# untitled2.net
KiCad netlist of a schematic drawn in EAGLE
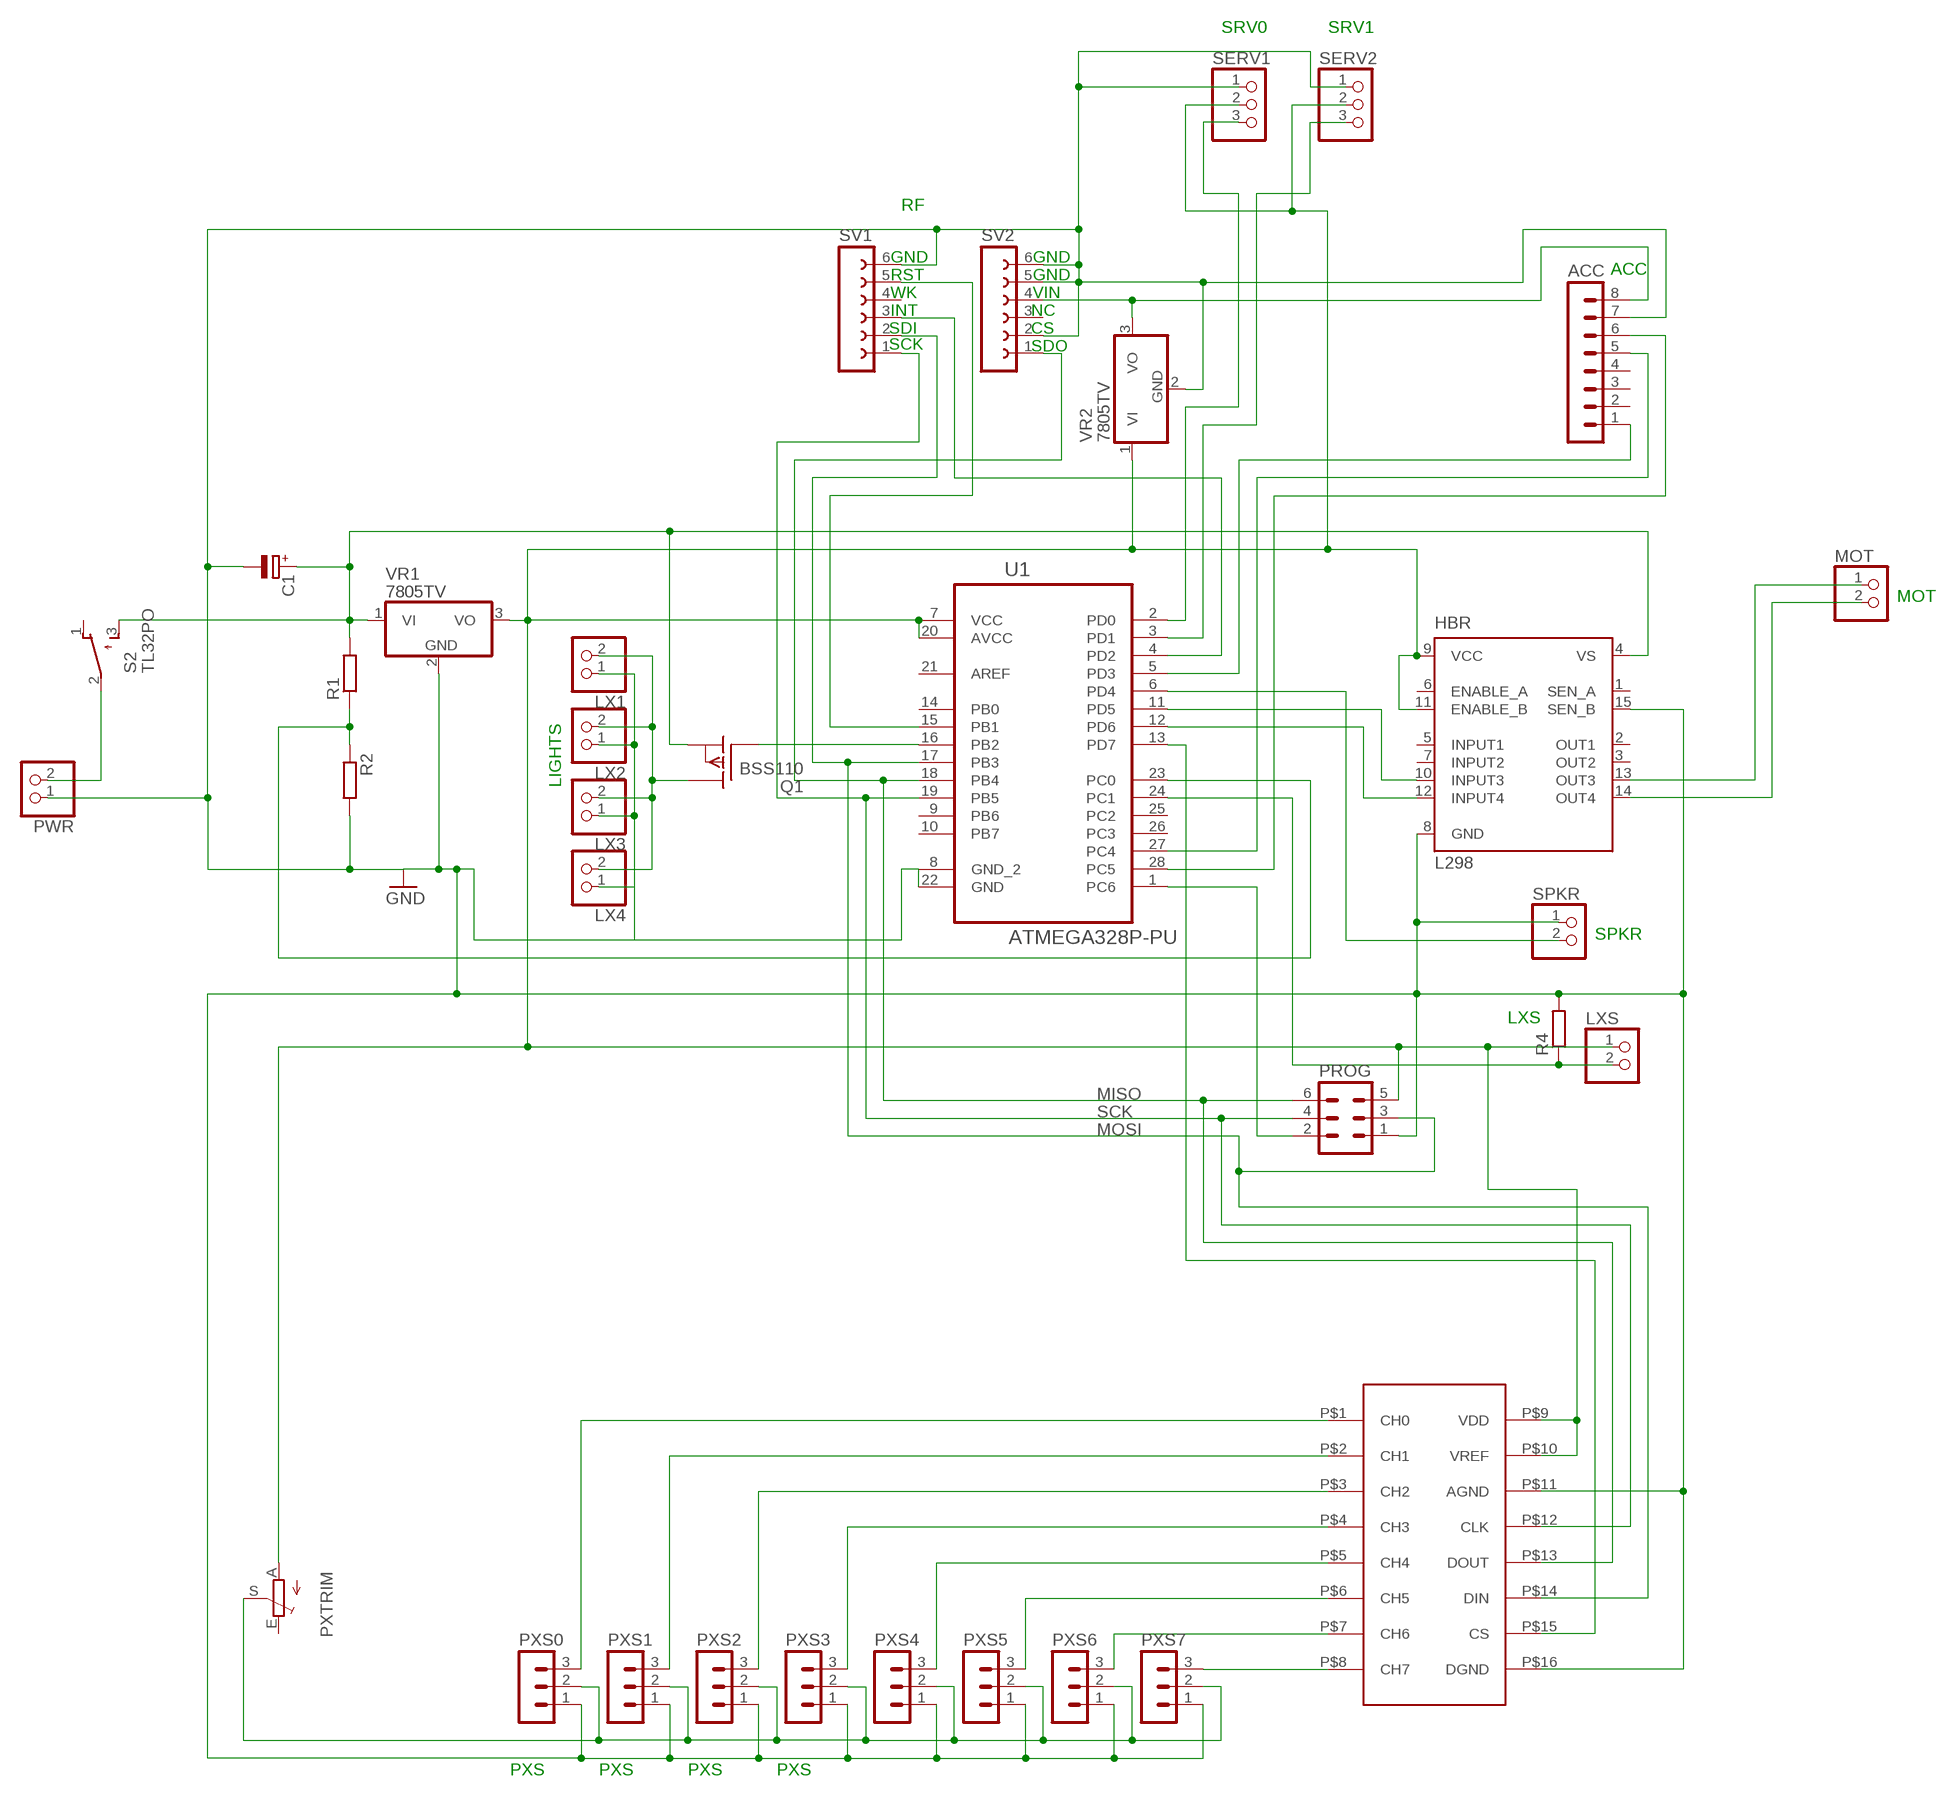
[diagram p0: schematic, sheet 1]

(export (version "E")
  (design (tool "Eeschema 10.0.6"))
  (components
    (comp (ref "ACC")
      (value "MA08-1")
      (footprint "eagle-import:MA08-1")
      (libsource (lib "eagle-import") (part "MA08-1"))
    )
    (comp (ref "C1")
      (value "CPOL-EUE2.5-7")
      (footprint "eagle-import:E2,5-7")
      (libsource (lib "eagle-import") (part "CPOL-EUE2.5-7"))
    )
    (comp (ref "HBR")
      (value "L298")
      (footprint "eagle-import:MULTIWATT-15")
      (fields (field (name "MPN") "L298N"))
      (libsource (lib "eagle-import") (part "L298"))
    )
    (comp (ref "LX1")
      (value "PINHD-1X2")
      (footprint "eagle-import:1X02")
      (libsource (lib "eagle-import") (part "PINHD-1X2"))
    )
    (comp (ref "LX2")
      (value "PINHD-1X2")
      (footprint "eagle-import:1X02")
      (libsource (lib "eagle-import") (part "PINHD-1X2"))
    )
    (comp (ref "LX3")
      (value "PINHD-1X2")
      (footprint "eagle-import:1X02")
      (libsource (lib "eagle-import") (part "PINHD-1X2"))
    )
    (comp (ref "LX4")
      (value "PINHD-1X2")
      (footprint "eagle-import:1X02")
      (libsource (lib "eagle-import") (part "PINHD-1X2"))
    )
    (comp (ref "LXS")
      (value "PINHD-1X2")
      (footprint "eagle-import:1X02")
      (libsource (lib "eagle-import") (part "PINHD-1X2"))
    )
    (comp (ref "MOT")
      (value "PINHD-1X2")
      (footprint "eagle-import:1X02")
      (libsource (lib "eagle-import") (part "PINHD-1X2"))
    )
    (comp (ref "PROG")
      (value "MA03-2")
      (footprint "eagle-import:MA03-2")
      (libsource (lib "eagle-import") (part "MA03-2"))
    )
    (comp (ref "PWR")
      (value "PINHD-1X2")
      (footprint "eagle-import:1X02")
      (libsource (lib "eagle-import") (part "PINHD-1X2"))
    )
    (comp (ref "PXS0")
      (value "MA03-1")
      (footprint "eagle-import:MA03-1")
      (libsource (lib "eagle-import") (part "MA03-1"))
    )
    (comp (ref "PXS1")
      (value "MA03-1")
      (footprint "eagle-import:MA03-1")
      (libsource (lib "eagle-import") (part "MA03-1"))
    )
    (comp (ref "PXS2")
      (value "MA03-1")
      (footprint "eagle-import:MA03-1")
      (libsource (lib "eagle-import") (part "MA03-1"))
    )
    (comp (ref "PXS3")
      (value "MA03-1")
      (footprint "eagle-import:MA03-1")
      (libsource (lib "eagle-import") (part "MA03-1"))
    )
    (comp (ref "PXS4")
      (value "MA03-1")
      (footprint "eagle-import:MA03-1")
      (libsource (lib "eagle-import") (part "MA03-1"))
    )
    (comp (ref "PXS5")
      (value "MA03-1")
      (footprint "eagle-import:MA03-1")
      (libsource (lib "eagle-import") (part "MA03-1"))
    )
    (comp (ref "PXS6")
      (value "MA03-1")
      (footprint "eagle-import:MA03-1")
      (libsource (lib "eagle-import") (part "MA03-1"))
    )
    (comp (ref "PXS7")
      (value "MA03-1")
      (footprint "eagle-import:MA03-1")
      (libsource (lib "eagle-import") (part "MA03-1"))
    )
    (comp (ref "PXTRIM")
      (value "TRIM_EU-CA9V")
      (footprint "eagle-import:CA9V")
      (libsource (lib "eagle-import") (part "TRIM_EU-CA9V"))
    )
    (comp (ref "Q1")
      (value "BSS110")
      (footprint "eagle-import:TO92")
      (libsource (lib "eagle-import") (part "BSS110"))
    )
    (comp (ref "R1")
      (value "R-EU_0309/V")
      (footprint "eagle-import:0309V")
      (libsource (lib "eagle-import") (part "R-EU_0309/V"))
    )
    (comp (ref "R2")
      (value "R-EU_0309/V")
      (footprint "eagle-import:0309V")
      (libsource (lib "eagle-import") (part "R-EU_0309/V"))
    )
    (comp (ref "R4")
      (value "R-EU_0309/V")
      (footprint "eagle-import:0309V")
      (libsource (lib "eagle-import") (part "R-EU_0309/V"))
    )
    (comp (ref "S2")
      (value "TL32PO")
      (footprint "eagle-import:TL3XPO")
      (libsource (lib "eagle-import") (part "TL32PO"))
    )
    (comp (ref "SERV1")
      (value "PINHD-1X3")
      (footprint "eagle-import:1X03")
      (libsource (lib "eagle-import") (part "PINHD-1X3"))
    )
    (comp (ref "SERV2")
      (value "PINHD-1X3")
      (footprint "eagle-import:1X03")
      (libsource (lib "eagle-import") (part "PINHD-1X3"))
    )
    (comp (ref "SPKR")
      (value "PINHD-1X2")
      (footprint "eagle-import:1X02")
      (libsource (lib "eagle-import") (part "PINHD-1X2"))
    )
    (comp (ref "SV1")
      (value "FE06-1")
      (footprint "eagle-import:FE06")
      (libsource (lib "eagle-import") (part "FE06-1"))
    )
    (comp (ref "SV2")
      (value "FE06-1")
      (footprint "eagle-import:FE06")
      (libsource (lib "eagle-import") (part "FE06-1"))
    )
    (comp (ref "U$1")
      (value "MCP3208")
      (footprint "eagle-import:DIP16")
      (libsource (lib "eagle-import") (part "MCP3208"))
    )
    (comp (ref "U1")
      (value "ATMEGA328P-PU")
      (footprint "eagle-import:DIP254P762X457-28")
      (libsource (lib "eagle-import") (part "ATMEGA328P-PU"))
    )
    (comp (ref "VR1")
      (value "7805TV")
      (footprint "eagle-import:TO220V")
      (libsource (lib "eagle-import") (part "78TV05"))
    )
    (comp (ref "VR2")
      (value "7805TV")
      (footprint "eagle-import:TO220V")
      (libsource (lib "eagle-import") (part "78TV05"))
    )
  )
  (nets
    (net (code "1") (name "/MISO") (class "Default")
      (node (ref "PROG") (pin "6") (pinfunction "6_6") (pintype "passive"))
      (node (ref "SV2") (pin "1") (pinfunction "1_1") (pintype "passive"))
      (node (ref "U$1") (pin "P$13") (pinfunction "DOUT_P$13") (pintype "bidirectional"))
      (node (ref "U1") (pin "18") (pinfunction "PB4_18") (pintype "bidirectional"))
    )
    (net (code "2") (name "/MOSI") (class "Default")
      (node (ref "PROG") (pin "3") (pinfunction "3_3") (pintype "passive"))
      (node (ref "SV1") (pin "2") (pinfunction "2_2") (pintype "passive"))
      (node (ref "U$1") (pin "P$14") (pinfunction "DIN_P$14") (pintype "bidirectional"))
      (node (ref "U1") (pin "17") (pinfunction "PB3_17") (pintype "bidirectional"))
    )
    (net (code "3") (name "/SCK") (class "Default")
      (node (ref "PROG") (pin "4") (pinfunction "4_4") (pintype "passive"))
      (node (ref "SV1") (pin "1") (pinfunction "1_1") (pintype "passive"))
      (node (ref "U$1") (pin "P$12") (pinfunction "CLK_P$12") (pintype "bidirectional"))
      (node (ref "U1") (pin "19") (pinfunction "PB5_19") (pintype "bidirectional"))
    )
    (net (code "4") (name "GND") (class "Default")
      (node (ref "ACC") (pin "7") (pinfunction "7_7") (pintype "passive"))
      (node (ref "C1") (pin "-") (pinfunction "-_-") (pintype "passive"))
      (node (ref "HBR") (pin "15") (pinfunction "SEN_B_15") (pintype "input"))
      (node (ref "HBR") (pin "8") (pinfunction "GND_8") (pintype "power_in"))
      (node (ref "LX1") (pin "1") (pinfunction "1_1") (pintype "passive"))
      (node (ref "LX2") (pin "1") (pinfunction "1_1") (pintype "passive"))
      (node (ref "LX3") (pin "1") (pinfunction "1_1") (pintype "passive"))
      (node (ref "LX4") (pin "1") (pinfunction "1_1") (pintype "passive"))
      (node (ref "PROG") (pin "1") (pinfunction "1_1") (pintype "passive"))
      (node (ref "PWR") (pin "1") (pinfunction "1_1") (pintype "passive"))
      (node (ref "PXS0") (pin "1") (pinfunction "1_1") (pintype "passive"))
      (node (ref "PXS1") (pin "1") (pinfunction "1_1") (pintype "passive"))
      (node (ref "PXS2") (pin "1") (pinfunction "1_1") (pintype "passive"))
      (node (ref "PXS3") (pin "1") (pinfunction "1_1") (pintype "passive"))
      (node (ref "PXS4") (pin "1") (pinfunction "1_1") (pintype "passive"))
      (node (ref "PXS5") (pin "1") (pinfunction "1_1") (pintype "passive"))
      (node (ref "PXS6") (pin "1") (pinfunction "1_1") (pintype "passive"))
      (node (ref "PXS7") (pin "1") (pinfunction "1_1") (pintype "passive"))
      (node (ref "R2") (pin "2") (pinfunction "2_2") (pintype "passive"))
      (node (ref "R4") (pin "2") (pinfunction "2_2") (pintype "passive"))
      (node (ref "SERV1") (pin "1") (pinfunction "1_1") (pintype "passive"))
      (node (ref "SERV2") (pin "1") (pinfunction "1_1") (pintype "passive"))
      (node (ref "SPKR") (pin "1") (pinfunction "1_1") (pintype "passive"))
      (node (ref "SV1") (pin "6") (pinfunction "6_6") (pintype "passive"))
      (node (ref "SV2") (pin "2") (pinfunction "2_2") (pintype "passive"))
      (node (ref "SV2") (pin "5") (pinfunction "5_5") (pintype "passive"))
      (node (ref "SV2") (pin "6") (pinfunction "6_6") (pintype "passive"))
      (node (ref "U$1") (pin "P$11") (pinfunction "AGND_P$11") (pintype "bidirectional"))
      (node (ref "U$1") (pin "P$16") (pinfunction "DGND_P$16") (pintype "bidirectional"))
      (node (ref "U1") (pin "22") (pinfunction "GND_22") (pintype "passive"))
      (node (ref "U1") (pin "8") (pinfunction "GND_2_8") (pintype "passive"))
      (node (ref "VR1") (pin "2") (pinfunction "GND_2") (pintype "passive"))
      (node (ref "VR2") (pin "2") (pinfunction "GND_2") (pintype "passive"))
    )
    (net (code "5") (name "Net-(HBR-ENABLE_B)") (class "Default")
      (node (ref "HBR") (pin "11") (pinfunction "ENABLE_B_11") (pintype "input"))
      (node (ref "HBR") (pin "9") (pinfunction "VCC_9") (pintype "power_in"))
      (node (ref "LXS") (pin "1") (pinfunction "1_1") (pintype "passive"))
      (node (ref "PROG") (pin "5") (pinfunction "5_5") (pintype "passive"))
      (node (ref "PXTRIM") (pin "A") (pinfunction "A_A") (pintype "passive"))
      (node (ref "SERV1") (pin "2") (pinfunction "2_2") (pintype "passive"))
      (node (ref "SERV2") (pin "2") (pinfunction "2_2") (pintype "passive"))
      (node (ref "U$1") (pin "P$10") (pinfunction "VREF_P$10") (pintype "bidirectional"))
      (node (ref "U$1") (pin "P$9") (pinfunction "VDD_P$9") (pintype "bidirectional"))
      (node (ref "U1") (pin "20") (pinfunction "AVCC_20") (pintype "power_in"))
      (node (ref "U1") (pin "7") (pinfunction "VCC_7") (pintype "power_in"))
      (node (ref "VR1") (pin "3") (pinfunction "VO_3") (pintype "passive"))
      (node (ref "VR2") (pin "1") (pinfunction "VI_1") (pintype "input"))
    )
    (net (code "6") (name "Net-(HBR-INPUT3)") (class "Default")
      (node (ref "HBR") (pin "10") (pinfunction "INPUT3_10") (pintype "input"))
      (node (ref "U1") (pin "11") (pinfunction "PD5_11") (pintype "bidirectional"))
    )
    (net (code "7") (name "Net-(HBR-INPUT4)") (class "Default")
      (node (ref "HBR") (pin "12") (pinfunction "INPUT4_12") (pintype "input"))
      (node (ref "U1") (pin "12") (pinfunction "PD6_12") (pintype "bidirectional"))
    )
    (net (code "8") (name "Net-(HBR-OUT3)") (class "Default")
      (node (ref "HBR") (pin "13") (pinfunction "OUT3_13") (pintype "output"))
      (node (ref "MOT") (pin "1") (pinfunction "1_1") (pintype "passive"))
    )
    (net (code "9") (name "Net-(HBR-OUT4)") (class "Default")
      (node (ref "HBR") (pin "14") (pinfunction "OUT4_14") (pintype "output"))
      (node (ref "MOT") (pin "2") (pinfunction "2_2") (pintype "passive"))
    )
    (net (code "10") (name "Net-(HBR-VS)") (class "Default")
      (node (ref "C1") (pin "+") (pinfunction "+_+") (pintype "passive"))
      (node (ref "HBR") (pin "4") (pinfunction "VS_4") (pintype "power_in"))
      (node (ref "Q1") (pin "1") (pinfunction "S_1") (pintype "passive"))
      (node (ref "R1") (pin "2") (pinfunction "2_2") (pintype "passive"))
      (node (ref "S2") (pin "3") (pinfunction "S_3") (pintype "passive"))
      (node (ref "VR1") (pin "1") (pinfunction "VI_1") (pintype "input"))
    )
    (net (code "11") (name "Net-(PXS0-Pad2)") (class "Default")
      (node (ref "PXS0") (pin "2") (pinfunction "2_2") (pintype "passive"))
      (node (ref "PXS1") (pin "2") (pinfunction "2_2") (pintype "passive"))
      (node (ref "PXS2") (pin "2") (pinfunction "2_2") (pintype "passive"))
      (node (ref "PXS3") (pin "2") (pinfunction "2_2") (pintype "passive"))
      (node (ref "PXS4") (pin "2") (pinfunction "2_2") (pintype "passive"))
      (node (ref "PXS5") (pin "2") (pinfunction "2_2") (pintype "passive"))
      (node (ref "PXS6") (pin "2") (pinfunction "2_2") (pintype "passive"))
      (node (ref "PXS7") (pin "2") (pinfunction "2_2") (pintype "passive"))
      (node (ref "PXTRIM") (pin "S") (pinfunction "S_S") (pintype "passive"))
    )
    (net (code "12") (name "Net-(Q1-D)") (class "Default")
      (node (ref "LX1") (pin "2") (pinfunction "2_2") (pintype "passive"))
      (node (ref "LX2") (pin "2") (pinfunction "2_2") (pintype "passive"))
      (node (ref "LX3") (pin "2") (pinfunction "2_2") (pintype "passive"))
      (node (ref "LX4") (pin "2") (pinfunction "2_2") (pintype "passive"))
      (node (ref "Q1") (pin "3") (pinfunction "D_3") (pintype "passive"))
    )
    (net (code "13") (name "Net-(Q1-G)") (class "Default")
      (node (ref "Q1") (pin "2") (pinfunction "G_2") (pintype "passive"))
      (node (ref "U1") (pin "16") (pinfunction "PB2_16") (pintype "bidirectional"))
    )
    (net (code "14") (name "Net-(S2-P)") (class "Default")
      (node (ref "PWR") (pin "2") (pinfunction "2_2") (pintype "passive"))
      (node (ref "S2") (pin "2") (pinfunction "P_2") (pintype "passive"))
    )
    (net (code "15") (name "Net-(U$1-CH0)") (class "Default")
      (node (ref "PXS0") (pin "3") (pinfunction "3_3") (pintype "passive"))
      (node (ref "U$1") (pin "P$1") (pinfunction "CH0_P$1") (pintype "bidirectional"))
    )
    (net (code "16") (name "Net-(U$1-CH1)") (class "Default")
      (node (ref "PXS1") (pin "3") (pinfunction "3_3") (pintype "passive"))
      (node (ref "U$1") (pin "P$2") (pinfunction "CH1_P$2") (pintype "bidirectional"))
    )
    (net (code "17") (name "Net-(U$1-CH2)") (class "Default")
      (node (ref "PXS2") (pin "3") (pinfunction "3_3") (pintype "passive"))
      (node (ref "U$1") (pin "P$3") (pinfunction "CH2_P$3") (pintype "bidirectional"))
    )
    (net (code "18") (name "Net-(U$1-CH3)") (class "Default")
      (node (ref "PXS3") (pin "3") (pinfunction "3_3") (pintype "passive"))
      (node (ref "U$1") (pin "P$4") (pinfunction "CH3_P$4") (pintype "bidirectional"))
    )
    (net (code "19") (name "Net-(U$1-CH4)") (class "Default")
      (node (ref "PXS4") (pin "3") (pinfunction "3_3") (pintype "passive"))
      (node (ref "U$1") (pin "P$5") (pinfunction "CH4_P$5") (pintype "bidirectional"))
    )
    (net (code "20") (name "Net-(U$1-CH5)") (class "Default")
      (node (ref "PXS5") (pin "3") (pinfunction "3_3") (pintype "passive"))
      (node (ref "U$1") (pin "P$6") (pinfunction "CH5_P$6") (pintype "bidirectional"))
    )
    (net (code "21") (name "Net-(U$1-CH6)") (class "Default")
      (node (ref "PXS6") (pin "3") (pinfunction "3_3") (pintype "passive"))
      (node (ref "U$1") (pin "P$7") (pinfunction "CH6_P$7") (pintype "bidirectional"))
    )
    (net (code "22") (name "Net-(U$1-CH7)") (class "Default")
      (node (ref "PXS7") (pin "3") (pinfunction "3_3") (pintype "passive"))
      (node (ref "U$1") (pin "P$8") (pinfunction "CH7_P$8") (pintype "bidirectional"))
    )
    (net (code "23") (name "Net-(U$1-CS)") (class "Default")
      (node (ref "U$1") (pin "P$15") (pinfunction "CS_P$15") (pintype "bidirectional"))
      (node (ref "U1") (pin "13") (pinfunction "PD7_13") (pintype "bidirectional"))
    )
    (net (code "24") (name "Net-(U1-PB1)") (class "Default")
      (node (ref "SV1") (pin "5") (pinfunction "5_5") (pintype "passive"))
      (node (ref "U1") (pin "15") (pinfunction "PB1_15") (pintype "bidirectional"))
    )
    (net (code "25") (name "Net-(U1-PC0)") (class "Default")
      (node (ref "R1") (pin "1") (pinfunction "1_1") (pintype "passive"))
      (node (ref "R2") (pin "1") (pinfunction "1_1") (pintype "passive"))
      (node (ref "U1") (pin "23") (pinfunction "PC0_23") (pintype "bidirectional"))
    )
    (net (code "26") (name "Net-(U1-PC1)") (class "Default")
      (node (ref "LXS") (pin "2") (pinfunction "2_2") (pintype "passive"))
      (node (ref "R4") (pin "1") (pinfunction "1_1") (pintype "passive"))
      (node (ref "U1") (pin "24") (pinfunction "PC1_24") (pintype "bidirectional"))
    )
    (net (code "27") (name "Net-(U1-PC4)") (class "Default")
      (node (ref "ACC") (pin "5") (pinfunction "5_5") (pintype "passive"))
      (node (ref "U1") (pin "27") (pinfunction "PC4_27") (pintype "bidirectional"))
    )
    (net (code "28") (name "Net-(U1-PC5)") (class "Default")
      (node (ref "ACC") (pin "6") (pinfunction "6_6") (pintype "passive"))
      (node (ref "U1") (pin "28") (pinfunction "PC5_28") (pintype "bidirectional"))
    )
    (net (code "29") (name "Net-(U1-PC6)") (class "Default")
      (node (ref "PROG") (pin "2") (pinfunction "2_2") (pintype "passive"))
      (node (ref "U1") (pin "1") (pinfunction "PC6_1") (pintype "bidirectional"))
    )
    (net (code "30") (name "Net-(U1-PD0)") (class "Default")
      (node (ref "SERV1") (pin "3") (pinfunction "3_3") (pintype "passive"))
      (node (ref "U1") (pin "2") (pinfunction "PD0_2") (pintype "bidirectional"))
    )
    (net (code "31") (name "Net-(U1-PD1)") (class "Default")
      (node (ref "SERV2") (pin "3") (pinfunction "3_3") (pintype "passive"))
      (node (ref "U1") (pin "3") (pinfunction "PD1_3") (pintype "bidirectional"))
    )
    (net (code "32") (name "Net-(U1-PD2)") (class "Default")
      (node (ref "SV1") (pin "3") (pinfunction "3_3") (pintype "passive"))
      (node (ref "U1") (pin "4") (pinfunction "PD2_4") (pintype "bidirectional"))
    )
    (net (code "33") (name "Net-(U1-PD3)") (class "Default")
      (node (ref "ACC") (pin "1") (pinfunction "1_1") (pintype "passive"))
      (node (ref "U1") (pin "5") (pinfunction "PD3_5") (pintype "bidirectional"))
    )
    (net (code "34") (name "Net-(U1-PD4)") (class "Default")
      (node (ref "SPKR") (pin "2") (pinfunction "2_2") (pintype "passive"))
      (node (ref "U1") (pin "6") (pinfunction "PD4_6") (pintype "bidirectional"))
    )
    (net (code "35") (name "Net-(VR2-VO)") (class "Default")
      (node (ref "ACC") (pin "8") (pinfunction "8_8") (pintype "passive"))
      (node (ref "SV2") (pin "4") (pinfunction "4_4") (pintype "passive"))
      (node (ref "VR2") (pin "3") (pinfunction "VO_3") (pintype "passive"))
    )
    (net (code "36") (name "unconnected-(ACC-Pad2)") (class "Default")
      (node (ref "ACC") (pin "2") (pinfunction "2_2") (pintype "passive"))
    )
    (net (code "37") (name "unconnected-(ACC-Pad3)") (class "Default")
      (node (ref "ACC") (pin "3") (pinfunction "3_3") (pintype "passive"))
    )
    (net (code "38") (name "unconnected-(ACC-Pad4)") (class "Default")
      (node (ref "ACC") (pin "4") (pinfunction "4_4") (pintype "passive"))
    )
    (net (code "39") (name "unconnected-(HBR-ENABLE_A-Pad6)") (class "Default")
      (node (ref "HBR") (pin "6") (pinfunction "ENABLE_A_6") (pintype "input"))
    )
    (net (code "40") (name "unconnected-(HBR-INPUT1-Pad5)") (class "Default")
      (node (ref "HBR") (pin "5") (pinfunction "INPUT1_5") (pintype "input"))
    )
    (net (code "41") (name "unconnected-(HBR-INPUT2-Pad7)") (class "Default")
      (node (ref "HBR") (pin "7") (pinfunction "INPUT2_7") (pintype "input"))
    )
    (net (code "42") (name "unconnected-(HBR-OUT1-Pad2)") (class "Default")
      (node (ref "HBR") (pin "2") (pinfunction "OUT1_2") (pintype "output"))
    )
    (net (code "43") (name "unconnected-(HBR-OUT2-Pad3)") (class "Default")
      (node (ref "HBR") (pin "3") (pinfunction "OUT2_3") (pintype "output"))
    )
    (net (code "44") (name "unconnected-(HBR-SEN_A-Pad1)") (class "Default")
      (node (ref "HBR") (pin "1") (pinfunction "SEN_A_1") (pintype "input"))
    )
    (net (code "45") (name "unconnected-(PXTRIM-PadE)") (class "Default")
      (node (ref "PXTRIM") (pin "E") (pinfunction "E_E") (pintype "passive"))
    )
    (net (code "46") (name "unconnected-(S2-O-Pad1)") (class "Default")
      (node (ref "S2") (pin "1") (pinfunction "O_1") (pintype "passive"))
    )
    (net (code "47") (name "unconnected-(SV1-Pad4)") (class "Default")
      (node (ref "SV1") (pin "4") (pinfunction "4_4") (pintype "passive"))
    )
    (net (code "48") (name "unconnected-(SV2-Pad3)") (class "Default")
      (node (ref "SV2") (pin "3") (pinfunction "3_3") (pintype "passive"))
    )
    (net (code "49") (name "unconnected-(U1-AREF-Pad21)") (class "Default")
      (node (ref "U1") (pin "21") (pinfunction "AREF_21") (pintype "input"))
    )
    (net (code "50") (name "unconnected-(U1-PB0-Pad14)") (class "Default")
      (node (ref "U1") (pin "14") (pinfunction "PB0_14") (pintype "bidirectional"))
    )
    (net (code "51") (name "unconnected-(U1-PB6-Pad9)") (class "Default")
      (node (ref "U1") (pin "9") (pinfunction "PB6_9") (pintype "bidirectional"))
    )
    (net (code "52") (name "unconnected-(U1-PB7-Pad10)") (class "Default")
      (node (ref "U1") (pin "10") (pinfunction "PB7_10") (pintype "bidirectional"))
    )
    (net (code "53") (name "unconnected-(U1-PC2-Pad25)") (class "Default")
      (node (ref "U1") (pin "25") (pinfunction "PC2_25") (pintype "bidirectional"))
    )
    (net (code "54") (name "unconnected-(U1-PC3-Pad26)") (class "Default")
      (node (ref "U1") (pin "26") (pinfunction "PC3_26") (pintype "bidirectional"))
    )
  )
)
